# Microcontroller.net
KiCad netlist of a schematic drawn in Altium Designer
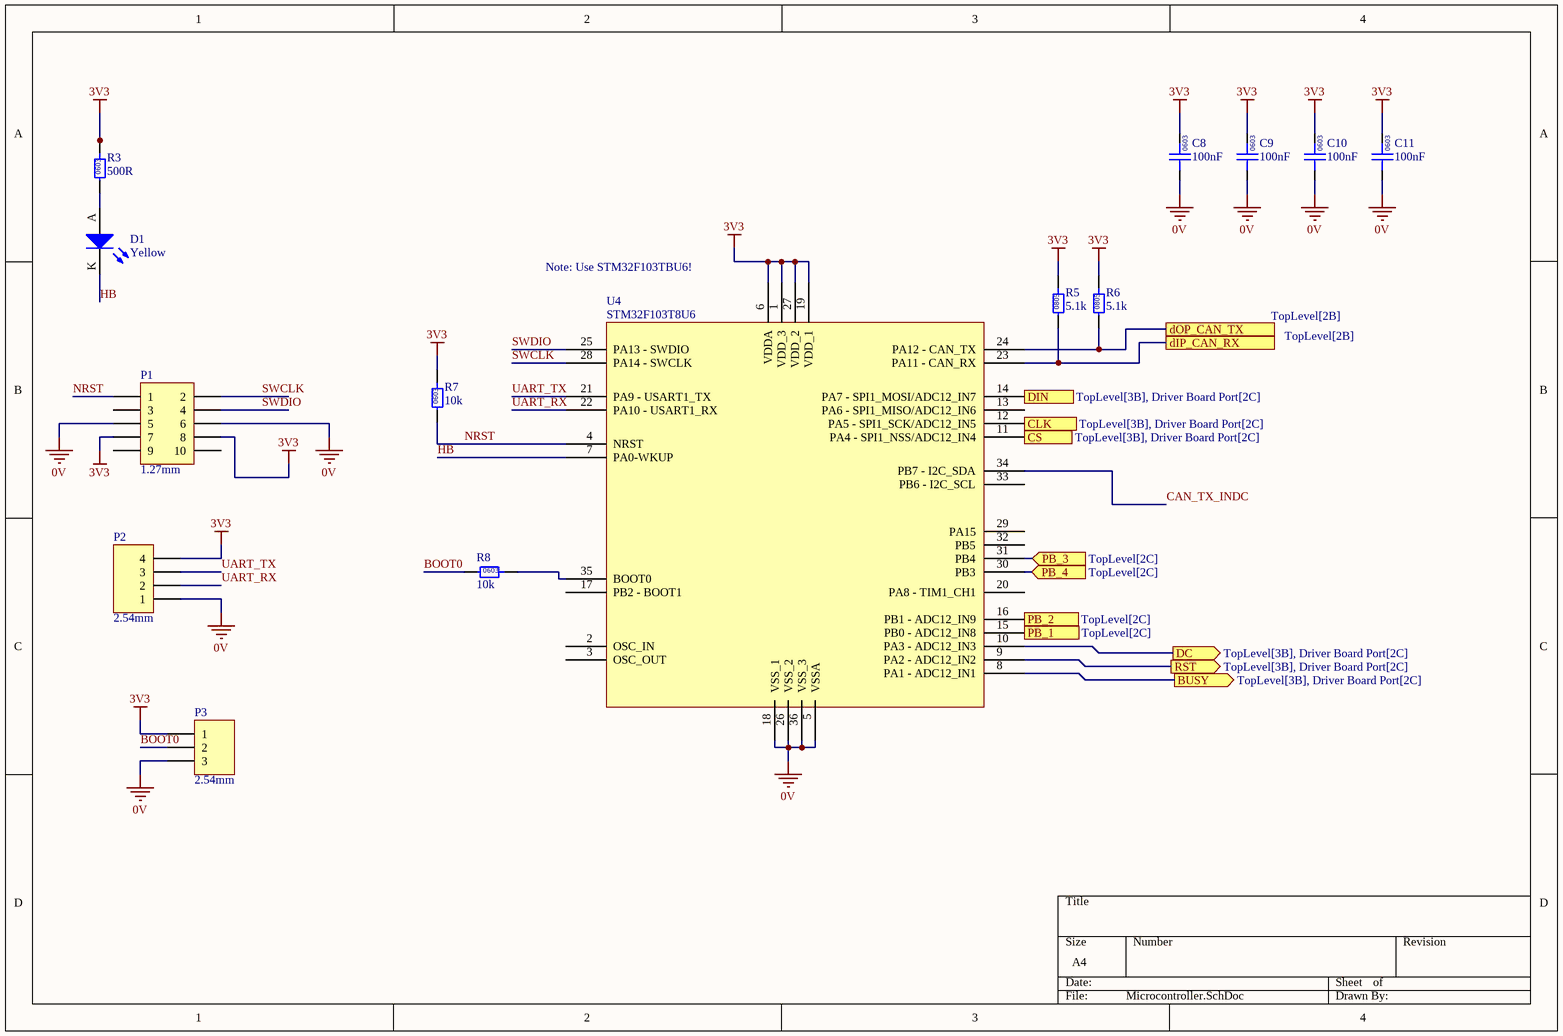
[diagram p0: Microcontroller.SchDoc]

(export (version "E")
  (design (tool "Eeschema 10.0.6"))
  (components
    (comp (ref "C8")
      (value "100nF")
      (footprint "0603")
      (fields
        (field (name "PART NUMBER") "GCM188L81H104KA57D")
        (field (name "MANUFACTURER") "muRata")
        (field (name "TOLERANCE") "±10%")
      )
      (libsource (lib "ts_standard_library") (part "Capacitor 0603"))
    )
    (comp (ref "C9")
      (value "100nF")
      (footprint "0603")
      (fields
        (field (name "PART NUMBER") "GCM188L81H104KA57D")
        (field (name "MANUFACTURER") "muRata")
        (field (name "TOLERANCE") "±10%")
      )
      (libsource (lib "ts_standard_library") (part "Capacitor 0603"))
    )
    (comp (ref "C10")
      (value "100nF")
      (footprint "0603")
      (fields
        (field (name "PART NUMBER") "GCM188L81H104KA57D")
        (field (name "MANUFACTURER") "muRata")
        (field (name "TOLERANCE") "±10%")
      )
      (libsource (lib "ts_standard_library") (part "Capacitor 0603"))
    )
    (comp (ref "C11")
      (value "100nF")
      (footprint "0603")
      (fields
        (field (name "PART NUMBER") "GCM188L81H104KA57D")
        (field (name "MANUFACTURER") "muRata")
        (field (name "TOLERANCE") "±10%")
      )
      (libsource (lib "ts_standard_library") (part "Capacitor 0603"))
    )
    (comp (ref "D1")
      (value "Yellow")
      (footprint "0805 LED")
      (description "Yellow LED Indication - Discrete 1.75V 0805 (2012 Metric)")
      (fields (field (name "PART NUMBER") "SML-211YTT86") (field (name "MANUFACTURER") "ROHM Semiconductor"))
      (libsource (lib "ts_standard_library") (part "LED"))
    )
    (comp (ref "P1")
      (value "1.27mm")
      (footprint "3221-10-0300-00")
      (fields
        (field (name "PART NUMBER") "SMD 1.27mm Header 2x5 (3221-10-0300-00)")
        (field (name "CONTACT") "NA")
      )
      (libsource (lib "ts_standard_connectors") (part "Header 2x5"))
    )
    (comp (ref "P2")
      (value "2.54mm")
      (footprint "TH 2.54mm Header 1x4")
      (fields (field (name "PART NUMBER") "TH 2.54mm Header 1x4") (field (name "CONTACT") "NA"))
      (libsource (lib "ts_standard_connectors") (part "Header 1x4"))
    )
    (comp (ref "P3")
      (value "2.54mm")
      (footprint "TH 2.54mm Header 1x3")
      (fields (field (name "PART NUMBER") "TH 2.54mm Header 1x3") (field (name "CONTACT") "NA"))
      (libsource (lib "ts_standard_connectors") (part "Header 1x3"))
    )
    (comp (ref "R3")
      (value "500R")
      (footprint "0603")
      (fields
        (field (name "PART NUMBER") "RT0603BRD07500RL")
        (field (name "MANUFACTURER") "YAGEO")
        (field (name "TOLERANCE") "0.01")
      )
      (libsource (lib "ts_standard_library") (part "Resistor 0603"))
    )
    (comp (ref "R5")
      (value "5.1k")
      (footprint "0805")
      (fields
        (field (name "PART NUMBER") "RC0805FR075K1L")
        (field (name "MANUFACTURER") "YAGEO")
        (field (name "TOLERANCE") "0.01")
      )
      (libsource (lib "ts_standard_library") (part "Resistor 0805"))
    )
    (comp (ref "R6")
      (value "5.1k")
      (footprint "0805")
      (fields
        (field (name "PART NUMBER") "RC0805FR075K1L")
        (field (name "MANUFACTURER") "YAGEO")
        (field (name "TOLERANCE") "0.01")
      )
      (libsource (lib "ts_standard_library") (part "Resistor 0805"))
    )
    (comp (ref "R7")
      (value "10k")
      (footprint "0603")
      (fields
        (field (name "PART NUMBER") "RC0603FR-0710KL")
        (field (name "MANUFACTURER") "YAGEO")
        (field (name "TOLERANCE") "0.01")
      )
      (libsource (lib "ts_standard_library") (part "Resistor 0603"))
    )
    (comp (ref "R8")
      (value "10k")
      (footprint "0603")
      (fields
        (field (name "PART NUMBER") "RC0603FR-0710KL")
        (field (name "MANUFACTURER") "YAGEO")
        (field (name "TOLERANCE") "0.01")
      )
      (libsource (lib "ts_standard_library") (part "Resistor 0603"))
    )
    (comp (ref "U4")
      (value "STM32F103T8U6")
      (footprint "STM_QFN-36")
      (description "ARM® Cortex®-M3 STM32F1 Microcontroller IC 32-Bit 72MHz 64KB (64K x 8) FLASH QFN")
      (fields (field (name "MANUFACTURER") "ST Microelectronics"))
      (libsource (lib "ts_standard_library") (part "STM32F103T8U6"))
    )
  )
  (nets
    (net (code "1") (name "/BOOT0") (class "Default")
      (node (ref "P3") (pin "2") (pinfunction "2_2") (pintype "passive"))
      (node (ref "R8") (pin "1") (pinfunction "1_1") (pintype "passive"))
    )
    (net (code "2") (name "/BUSY") (class "Default")
      (node (ref "U4") (pin "8") (pinfunction "PA1_-_ADC12_IN1_8") (pintype "passive"))
    )
    (net (code "3") (name "/CAN_TX_INDC") (class "Default")
      (node (ref "U4") (pin "34") (pinfunction "PB7_-_I2C_SDA_34") (pintype "passive"))
    )
    (net (code "4") (name "/CLK") (class "Default")
      (node (ref "U4") (pin "12") (pinfunction "PA5_-_SPI1_SCK/ADC12_IN5_12") (pintype "passive"))
    )
    (net (code "5") (name "/CS") (class "Default")
      (node (ref "U4") (pin "11") (pinfunction "PA4_-_SPI1_NSS/ADC12_IN4_11") (pintype "passive"))
    )
    (net (code "6") (name "/DC") (class "Default")
      (node (ref "U4") (pin "10") (pinfunction "PA3_-_ADC12_IN3_10") (pintype "passive"))
    )
    (net (code "7") (name "/DIN") (class "Default")
      (node (ref "U4") (pin "14") (pinfunction "PA7_-_SPI1_MOSI/ADC12_IN7_14") (pintype "passive"))
    )
    (net (code "8") (name "/HB") (class "Default")
      (node (ref "D1") (pin "K") (pinfunction "K_K") (pintype "passive"))
      (node (ref "U4") (pin "7") (pinfunction "PA0-WKUP_7") (pintype "passive"))
    )
    (net (code "9") (name "/NRST") (class "Default")
      (node (ref "P1") (pin "1") (pinfunction "1_1") (pintype "passive"))
      (node (ref "R7") (pin "1") (pinfunction "1_1") (pintype "passive"))
      (node (ref "U4") (pin "4") (pinfunction "NRST_4") (pintype "passive"))
    )
    (net (code "10") (name "/PB_1") (class "Default")
      (node (ref "U4") (pin "15") (pinfunction "PB0_-_ADC12_IN8_15") (pintype "passive"))
    )
    (net (code "11") (name "/PB_2") (class "Default")
      (node (ref "U4") (pin "16") (pinfunction "PB1_-_ADC12_IN9_16") (pintype "passive"))
    )
    (net (code "12") (name "/PB_3") (class "Default")
      (node (ref "U4") (pin "31") (pinfunction "PB4_31") (pintype "passive"))
    )
    (net (code "13") (name "/PB_4") (class "Default")
      (node (ref "U4") (pin "30") (pinfunction "PB3_30") (pintype "passive"))
    )
    (net (code "14") (name "/RST") (class "Default")
      (node (ref "U4") (pin "9") (pinfunction "PA2_-_ADC12_IN2_9") (pintype "passive"))
    )
    (net (code "15") (name "/SWCLK") (class "Default")
      (node (ref "P1") (pin "2") (pinfunction "2_2") (pintype "passive"))
      (node (ref "U4") (pin "28") (pinfunction "PA14_-_SWCLK_28") (pintype "passive"))
    )
    (net (code "16") (name "/SWDIO") (class "Default")
      (node (ref "P1") (pin "4") (pinfunction "4_4") (pintype "passive"))
      (node (ref "U4") (pin "25") (pinfunction "PA13_-_SWDIO_25") (pintype "passive"))
    )
    (net (code "17") (name "/UART_RX") (class "Default")
      (node (ref "P2") (pin "2") (pinfunction "2_2") (pintype "passive"))
      (node (ref "U4") (pin "22") (pinfunction "PA10_-_USART1_RX_22") (pintype "passive"))
    )
    (net (code "18") (name "/UART_TX") (class "Default")
      (node (ref "P2") (pin "3") (pinfunction "3_3") (pintype "passive"))
      (node (ref "U4") (pin "21") (pinfunction "PA9_-_USART1_TX_21") (pintype "passive"))
    )
    (net (code "19") (name "/dIP_CAN_RX") (class "Default")
      (node (ref "R5") (pin "1") (pinfunction "1_1") (pintype "passive"))
      (node (ref "U4") (pin "23") (pinfunction "PA11_-_CAN_RX_23") (pintype "passive"))
    )
    (net (code "20") (name "/dOP_CAN_TX") (class "Default")
      (node (ref "R6") (pin "1") (pinfunction "1_1") (pintype "passive"))
      (node (ref "U4") (pin "24") (pinfunction "PA12_-_CAN_TX_24") (pintype "passive"))
    )
    (net (code "21") (name "0V") (class "Default")
      (node (ref "C10") (pin "1") (pinfunction "1_1") (pintype "passive"))
      (node (ref "C11") (pin "1") (pinfunction "1_1") (pintype "passive"))
      (node (ref "C8") (pin "1") (pinfunction "1_1") (pintype "passive"))
      (node (ref "C9") (pin "1") (pinfunction "1_1") (pintype "passive"))
      (node (ref "P1") (pin "5") (pinfunction "5_5") (pintype "passive"))
      (node (ref "P1") (pin "6") (pinfunction "6_6") (pintype "passive"))
      (node (ref "P2") (pin "1") (pinfunction "1_1") (pintype "passive"))
      (node (ref "P3") (pin "3") (pinfunction "3_3") (pintype "passive"))
      (node (ref "U4") (pin "18") (pinfunction "VSS_1_18") (pintype "passive"))
      (node (ref "U4") (pin "26") (pinfunction "VSS_2_26") (pintype "passive"))
      (node (ref "U4") (pin "36") (pinfunction "VSS_3_36") (pintype "passive"))
      (node (ref "U4") (pin "5") (pinfunction "VSSA_5") (pintype "passive"))
    )
    (net (code "22") (name "3V3") (class "Default")
      (node (ref "C10") (pin "2") (pinfunction "2_2") (pintype "passive"))
      (node (ref "C11") (pin "2") (pinfunction "2_2") (pintype "passive"))
      (node (ref "C8") (pin "2") (pinfunction "2_2") (pintype "passive"))
      (node (ref "C9") (pin "2") (pinfunction "2_2") (pintype "passive"))
      (node (ref "P1") (pin "7") (pinfunction "7_7") (pintype "passive"))
      (node (ref "P1") (pin "8") (pinfunction "8_8") (pintype "passive"))
      (node (ref "P2") (pin "4") (pinfunction "4_4") (pintype "passive"))
      (node (ref "P3") (pin "1") (pinfunction "1_1") (pintype "passive"))
      (node (ref "R3") (pin "2") (pinfunction "2_2") (pintype "passive"))
      (node (ref "R5") (pin "2") (pinfunction "2_2") (pintype "passive"))
      (node (ref "R6") (pin "2") (pinfunction "2_2") (pintype "passive"))
      (node (ref "R7") (pin "2") (pinfunction "2_2") (pintype "passive"))
      (node (ref "U4") (pin "1") (pinfunction "VDD_3_1") (pintype "passive"))
      (node (ref "U4") (pin "19") (pinfunction "VDD_1_19") (pintype "passive"))
      (node (ref "U4") (pin "27") (pinfunction "VDD_2_27") (pintype "passive"))
      (node (ref "U4") (pin "6") (pinfunction "VDDA_6") (pintype "passive"))
    )
    (net (code "23") (name "Net-(D1-PadA)") (class "Default")
      (node (ref "D1") (pin "A") (pinfunction "A_A") (pintype "passive"))
      (node (ref "R3") (pin "1") (pinfunction "1_1") (pintype "passive"))
    )
    (net (code "24") (name "Net-(U4-BOOT0)") (class "Default")
      (node (ref "R8") (pin "2") (pinfunction "2_2") (pintype "passive"))
      (node (ref "U4") (pin "35") (pinfunction "BOOT0_35") (pintype "passive"))
    )
    (net (code "25") (name "unconnected-(P1-Pad3)") (class "Default")
      (node (ref "P1") (pin "3") (pinfunction "3_3") (pintype "passive"))
    )
    (net (code "26") (name "unconnected-(P1-Pad9)") (class "Default")
      (node (ref "P1") (pin "9") (pinfunction "9_9") (pintype "passive"))
    )
    (net (code "27") (name "unconnected-(P1-Pad10)") (class "Default")
      (node (ref "P1") (pin "10") (pinfunction "10_10") (pintype "passive"))
    )
    (net (code "28") (name "unconnected-(U4-OSC_IN-Pad2)") (class "Default")
      (node (ref "U4") (pin "2") (pinfunction "OSC_IN_2") (pintype "passive"))
    )
    (net (code "29") (name "unconnected-(U4-OSC_OUT-Pad3)") (class "Default")
      (node (ref "U4") (pin "3") (pinfunction "OSC_OUT_3") (pintype "passive"))
    )
    (net (code "30") (name "unconnected-(U4-PA6_-_SPI1_MISO{slash}ADC12_IN6-Pad13)") (class "Default")
      (node (ref "U4") (pin "13") (pinfunction "PA6_-_SPI1_MISO/ADC12_IN6_13") (pintype "passive"))
    )
    (net (code "31") (name "unconnected-(U4-PA8_-_TIM1_CH1-Pad20)") (class "Default")
      (node (ref "U4") (pin "20") (pinfunction "PA8_-_TIM1_CH1_20") (pintype "passive"))
    )
    (net (code "32") (name "unconnected-(U4-PA15-Pad29)") (class "Default")
      (node (ref "U4") (pin "29") (pinfunction "PA15_29") (pintype "passive"))
    )
    (net (code "33") (name "unconnected-(U4-PB2_-_BOOT1-Pad17)") (class "Default")
      (node (ref "U4") (pin "17") (pinfunction "PB2_-_BOOT1_17") (pintype "passive"))
    )
    (net (code "34") (name "unconnected-(U4-PB5-Pad32)") (class "Default")
      (node (ref "U4") (pin "32") (pinfunction "PB5_32") (pintype "passive"))
    )
    (net (code "35") (name "unconnected-(U4-PB6_-_I2C_SCL-Pad33)") (class "Default")
      (node (ref "U4") (pin "33") (pinfunction "PB6_-_I2C_SCL_33") (pintype "passive"))
    )
  )
)
